# SyncScan_Standalone_MK3_PTH.net
KiCad netlist of a schematic drawn in EAGLE
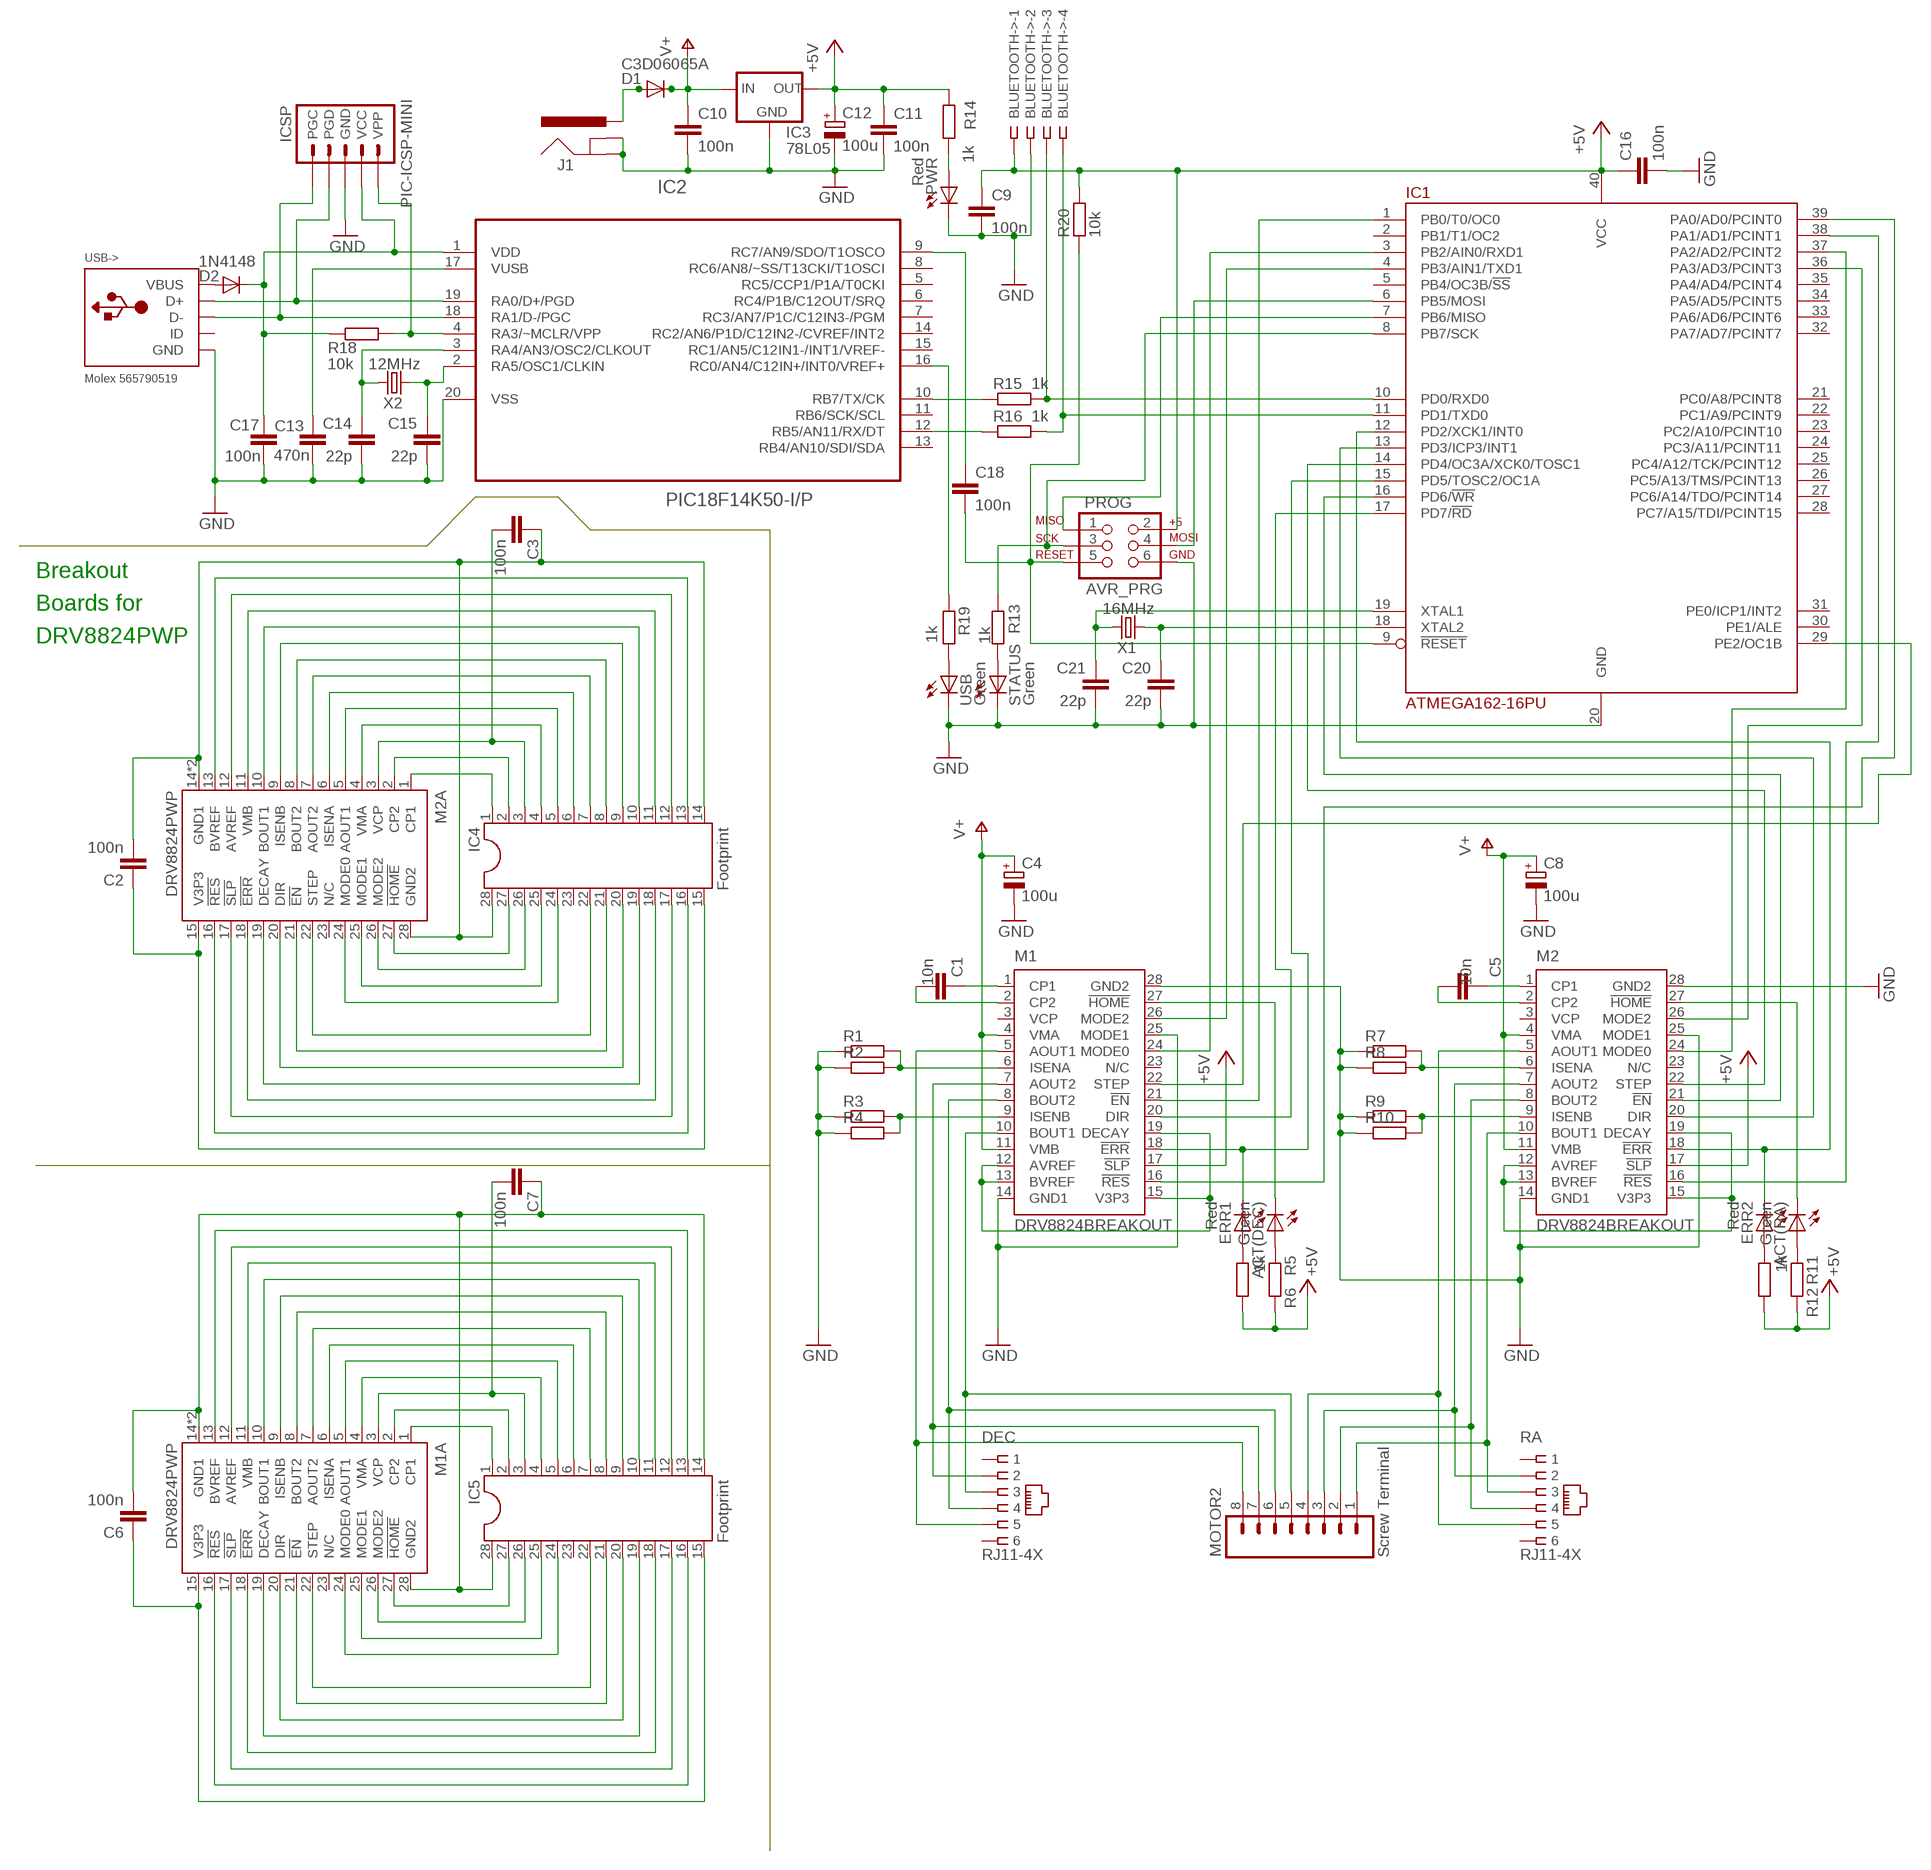
[diagram p0: schematic, sheet 1]

(export (version "E")
  (design (tool "Eeschema 10.0.6"))
  (components
    (comp (ref "ACT(DEC)")
      (value "Green")
      (footprint "eagle-import:LED3MM")
      (fields (field (name "MF") "KINGBRIGHT") (field (name "MPN") "L-424GDT"))
      (libsource (lib "eagle-import") (part "LED3MM"))
    )
    (comp (ref "ACT(RA)")
      (value "Green")
      (footprint "eagle-import:LED3MM")
      (fields (field (name "MF") "KINGBRIGHT") (field (name "MPN") "L-424GDT"))
      (libsource (lib "eagle-import") (part "LED3MM"))
    )
    (comp (ref "BLUETOOTH->")
      (value "http://www.ebay.co.uk/itm/250991624201")
      (footprint "eagle-import:SSW-104-02-S-S-RA")
      (fields (field (name "MPN") "SSW-104-02-S-S-RA") (field (name "OC_FARNELL") "unknown"))
      (libsource (lib "eagle-import") (part "SSW-104-02-S-S-RA"))
    )
    (comp (ref "C1")
      (value "10n")
      (footprint "eagle-import:C025-024X044")
      (fields (field (name "MF") "AVX") (field (name "MPN") "SR151C103KAR"))
      (libsource (lib "eagle-import") (part "resistor_C-EU025-024X044"))
    )
    (comp (ref "C2")
      (value "100n")
      (footprint "eagle-import:C0603K")
      (fields (field (name "MF") "KEMET") (field (name "MPN") "C0603C104K4RACTU"))
      (libsource (lib "eagle-import") (part "resistor_C-EUC0603K"))
    )
    (comp (ref "C3")
      (value "100n")
      (footprint "eagle-import:C0603K")
      (fields (field (name "MF") "KEMET") (field (name "MPN") "C0603C104K4RACTU"))
      (libsource (lib "eagle-import") (part "resistor_C-EUC0603K"))
    )
    (comp (ref "C4")
      (value "100u")
      (footprint "eagle-import:E2,5-6")
      (fields (field (name "MF") "MULTICOMP") (field (name "MPN") "MCGPR25V107M6.3X11"))
      (libsource (lib "eagle-import") (part "CPOL-EUE2.5-6"))
    )
    (comp (ref "C5")
      (value "10n")
      (footprint "eagle-import:C025-024X044")
      (fields (field (name "MF") "AVX") (field (name "MPN") "SR151C103KAR"))
      (libsource (lib "eagle-import") (part "resistor_C-EU025-024X044"))
    )
    (comp (ref "C6")
      (value "100n")
      (footprint "eagle-import:C0603K")
      (fields (field (name "MF") "KEMET") (field (name "MPN") "C0603C104K4RACTU"))
      (libsource (lib "eagle-import") (part "resistor_C-EUC0603K"))
    )
    (comp (ref "C7")
      (value "100n")
      (footprint "eagle-import:C0603K")
      (fields (field (name "MF") "KEMET") (field (name "MPN") "C0603C104K4RACTU"))
      (libsource (lib "eagle-import") (part "resistor_C-EUC0603K"))
    )
    (comp (ref "C8")
      (value "100u")
      (footprint "eagle-import:E2,5-6")
      (fields (field (name "MF") "MULTICOMP") (field (name "MPN") "MCGPR25V107M6.3X11"))
      (libsource (lib "eagle-import") (part "CPOL-EUE2.5-6"))
    )
    (comp (ref "C9")
      (value "100n")
      (footprint "eagle-import:C025-024X044")
      (fields (field (name "MF") "AVX") (field (name "MPN") "SR205C104KAR"))
      (libsource (lib "eagle-import") (part "resistor_C-EU025-024X044"))
    )
    (comp (ref "C10")
      (value "100n")
      (footprint "eagle-import:C025-024X044")
      (fields (field (name "MF") "AVX") (field (name "MPN") "SR205C104KAR"))
      (libsource (lib "eagle-import") (part "resistor_C-EU025-024X044"))
    )
    (comp (ref "C11")
      (value "100n")
      (footprint "eagle-import:C025-024X044")
      (fields (field (name "MF") "AVX") (field (name "MPN") "SR205C104KAR"))
      (libsource (lib "eagle-import") (part "resistor_C-EU025-024X044"))
    )
    (comp (ref "C12")
      (value "100u")
      (footprint "eagle-import:E2,5-6")
      (fields (field (name "MF") "MULTICOMP") (field (name "MPN") "MCGPR25V107M6.3X11"))
      (libsource (lib "eagle-import") (part "CPOL-EUE2.5-6"))
    )
    (comp (ref "C13")
      (value "470n")
      (footprint "eagle-import:C025-024X044")
      (fields (field (name "MF") "KEMET") (field (name "MPN") "C320C474M5U5TA"))
      (libsource (lib "eagle-import") (part "C-EU025-024X044"))
    )
    (comp (ref "C14")
      (value "22p")
      (footprint "eagle-import:C025-024X044")
      (fields (field (name "MF") "AVX") (field (name "MPN") "SR151A220JAR"))
      (libsource (lib "eagle-import") (part "C-EU025-024X044"))
    )
    (comp (ref "C15")
      (value "22p")
      (footprint "eagle-import:C025-024X044")
      (fields (field (name "MF") "AVX") (field (name "MPN") "SR151A220JAR"))
      (libsource (lib "eagle-import") (part "C-EU025-024X044"))
    )
    (comp (ref "C16")
      (value "100n")
      (footprint "eagle-import:C025-024X044")
      (fields (field (name "MF") "AVX") (field (name "MPN") "SR205C104KAR"))
      (libsource (lib "eagle-import") (part "resistor_C-EU025-024X044"))
    )
    (comp (ref "C17")
      (value "100n")
      (footprint "eagle-import:C025-024X044")
      (fields (field (name "MF") "AVX") (field (name "MPN") "SR205C104KAR"))
      (libsource (lib "eagle-import") (part "resistor_C-EU025-024X044"))
    )
    (comp (ref "C18")
      (value "100n")
      (footprint "eagle-import:C025-024X044")
      (fields (field (name "MF") "AVX") (field (name "MPN") "SR205C104KAR"))
      (libsource (lib "eagle-import") (part "resistor_C-EU025-024X044"))
    )
    (comp (ref "C20")
      (value "22p")
      (footprint "eagle-import:C025-024X044")
      (fields (field (name "MF") "AVX") (field (name "MPN") "SR151A220JAR"))
      (libsource (lib "eagle-import") (part "C-EU025-024X044"))
    )
    (comp (ref "C21")
      (value "22p")
      (footprint "eagle-import:C025-024X044")
      (fields (field (name "MF") "AVX") (field (name "MPN") "SR151A220JAR"))
      (libsource (lib "eagle-import") (part "C-EU025-024X044"))
    )
    (comp (ref "D1")
      (value "C3D06065A")
      (footprint "eagle-import:TO220ACS")
      (fields (field (name "MF") "CREE"))
      (libsource (lib "eagle-import") (part "BYW80"))
    )
    (comp (ref "D2")
      (value "1N4148")
      (footprint "eagle-import:DIODE-1N4148")
      (fields (field (name "MF") "MULTICOMP") (field (name "MPN") "1N4148."))
      (libsource (lib "eagle-import") (part "DIODE1N4148"))
    )
    (comp (ref "DEC")
      (value "RJ11-4X")
      (footprint "eagle-import:RJ11-NO_SHIELD")
      (fields
        (field (name "MPN") "6609214-3")
        (field (name "MF") "MH CONNECTORS")
        (field (name "MPN_1") "MHRJJ64NFRA")
        (field (name "OC_FARNELL") "3938347")
      )
      (libsource (lib "eagle-import") (part "RJ11-4X"))
    )
    (comp (ref "ERR1")
      (value "Red")
      (footprint "eagle-import:LED3MM")
      (fields (field (name "MF") "KINGBRIGHT") (field (name "MPN") "L-424HDT"))
      (libsource (lib "eagle-import") (part "LED3MM"))
    )
    (comp (ref "ERR2")
      (value "Red")
      (footprint "eagle-import:LED3MM")
      (fields (field (name "MF") "KINGBRIGHT") (field (name "MPN") "L-424HDT"))
      (libsource (lib "eagle-import") (part "LED3MM"))
    )
    (comp (ref "IC1")
      (value "ATMEGA162-16PU")
      (footprint "eagle-import:DIL40")
      (fields (field (name "MF") "ATMEL"))
      (libsource (lib "eagle-import") (part "ATMEGA162-16PU"))
    )
    (comp (ref "IC2")
      (value "PIC18F14K50-I/P")
      (footprint "eagle-import:DIL20")
      (fields
        (field (name "MF") "MICROCHIP")
        (field (name "MPN") "PIC18F14K50-I/P")
        (field (name "OC_FARNELL") "1648501")
      )
      (libsource (lib "eagle-import") (part "PIC18F14K50-I/P"))
    )
    (comp (ref "IC3")
      (value "78L05")
      (footprint "eagle-import:TO-92")
      (fields (field (name "MF") "FAIRCHILD SEMICONDUCTOR") (field (name "MPN") "LM78L05ACZX"))
      (libsource (lib "eagle-import") (part "V_REG_78XXTO-92"))
    )
    (comp (ref "IC4")
      (value "Footprint")
      (footprint "eagle-import:DIL28-6")
      (fields (field (name "MF") "MULTICOMP") (field (name "MPN") "MC34735"))
      (libsource (lib "eagle-import") (part "DIL28"))
    )
    (comp (ref "IC5")
      (value "Footprint")
      (footprint "eagle-import:DIL28-6")
      (fields (field (name "MF") "MULTICOMP") (field (name "MPN") "MC34735"))
      (libsource (lib "eagle-import") (part "DIL28"))
    )
    (comp (ref "ICSP")
      (value "PIC-ICSP-MINI")
      (footprint "eagle-import:PIC-ICSP-MINI")
      (libsource (lib "eagle-import") (part "PIC-ICSP-MINI"))
    )
    (comp (ref "J1")
      (value "POWER_JACKPTH")
      (footprint "eagle-import:POWER_JACK_PTH")
      (fields (field (name "MF") "MULTICOMP") (field (name "MPN") "MJ-179PH"))
      (libsource (lib "eagle-import") (part "POWER_JACKPTH"))
    )
    (comp (ref "M1")
      (value "DRV8824BREAKOUT")
      (footprint "eagle-import:DIL28-6")
      (fields (field (name "MF") "MULTICOMP") (field (name "MPN") "MC-2227-28-06-F1"))
      (libsource (lib "eagle-import") (part "DRV8824BREAKOUT"))
    )
    (comp (ref "M1A")
      (value "DRV8824PWP")
      (footprint "eagle-import:HTSSOP28PWP")
      (fields (field (name "MF") "TEXAS INSTRUMENTS"))
      (libsource (lib "eagle-import") (part "DRV8824PWP"))
    )
    (comp (ref "M2")
      (value "DRV8824BREAKOUT")
      (footprint "eagle-import:DIL28-6")
      (fields (field (name "MF") "MULTICOMP") (field (name "MPN") "MC-2227-28-06-F1"))
      (libsource (lib "eagle-import") (part "DRV8824BREAKOUT"))
    )
    (comp (ref "M2A")
      (value "DRV8824PWP")
      (footprint "eagle-import:HTSSOP28PWP")
      (fields (field (name "MF") "TEXAS INSTRUMENTS"))
      (libsource (lib "eagle-import") (part "DRV8824PWP"))
    )
    (comp (ref "MOTOR2")
      (value "Screw Terminal")
      (footprint "eagle-import:SCREWTERMINAL-3.5MM-8")
      (fields (field (name "MF") "LUMBERG") (field (name "MPN") "KRMC 08"))
      (libsource (lib "eagle-import") (part "M083.5MM-8"))
    )
    (comp (ref "PROG")
      (value "AVR_PRG")
      (footprint "eagle-import:2X3")
      (fields (field (name "MF") "TE CONNECTIVITY / AMP") (field (name "MPN") "826632-3"))
      (libsource (lib "eagle-import") (part "AVR_SPI_PRG_6PTH"))
    )
    (comp (ref "PWR")
      (value "Red")
      (footprint "eagle-import:LED3MM")
      (fields (field (name "MF") "KINGBRIGHT") (field (name "MPN") "L-424HDT"))
      (libsource (lib "eagle-import") (part "LED3MM"))
    )
    (comp (ref "R1")
      (value "1.5R")
      (footprint "eagle-import:0309_12")
      (fields (field (name "MF") "WELWYN") (field (name "MPN") "MFP1-1R5 JI"))
      (libsource (lib "eagle-import") (part "resistor_R-EU_0309/12"))
    )
    (comp (ref "R2")
      (value "1.5R")
      (footprint "eagle-import:0309_12")
      (fields (field (name "MF") "WELWYN") (field (name "MPN") "MFP1-1R5 JI"))
      (libsource (lib "eagle-import") (part "resistor_R-EU_0309/12"))
    )
    (comp (ref "R3")
      (value "1.5R")
      (footprint "eagle-import:0309_12")
      (fields (field (name "MF") "WELWYN") (field (name "MPN") "MFP1-1R5 JI"))
      (libsource (lib "eagle-import") (part "resistor_R-EU_0309/12"))
    )
    (comp (ref "R4")
      (value "1.5R")
      (footprint "eagle-import:0309_12")
      (fields (field (name "MF") "WELWYN") (field (name "MPN") "MFP1-1R5 JI"))
      (libsource (lib "eagle-import") (part "resistor_R-EU_0309/12"))
    )
    (comp (ref "R5")
      (value "1k")
      (footprint "eagle-import:0204_7")
      (fields (field (name "MF") "MULTICOMP") (field (name "MPN") "MF12 1K"))
      (libsource (lib "eagle-import") (part "resistor_R-EU_0204/7"))
    )
    (comp (ref "R6")
      (value "1k")
      (footprint "eagle-import:0204_7")
      (fields (field (name "MF") "MULTICOMP") (field (name "MPN") "MF12 1K"))
      (libsource (lib "eagle-import") (part "resistor_R-EU_0204/7"))
    )
    (comp (ref "R7")
      (value "1.5R")
      (footprint "eagle-import:0309_12")
      (fields (field (name "MF") "WELWYN") (field (name "MPN") "MFP1-1R5 JI"))
      (libsource (lib "eagle-import") (part "resistor_R-EU_0309/12"))
    )
    (comp (ref "R8")
      (value "1.5R")
      (footprint "eagle-import:0309_12")
      (fields (field (name "MF") "WELWYN") (field (name "MPN") "MFP1-1R5 JI"))
      (libsource (lib "eagle-import") (part "resistor_R-EU_0309/12"))
    )
    (comp (ref "R9")
      (value "1.5R")
      (footprint "eagle-import:0309_12")
      (fields (field (name "MF") "WELWYN") (field (name "MPN") "MFP1-1R5 JI"))
      (libsource (lib "eagle-import") (part "resistor_R-EU_0309/12"))
    )
    (comp (ref "R10")
      (value "1.5R")
      (footprint "eagle-import:0309_12")
      (fields (field (name "MF") "WELWYN") (field (name "MPN") "MFP1-1R5 JI"))
      (libsource (lib "eagle-import") (part "resistor_R-EU_0309/12"))
    )
    (comp (ref "R11")
      (value "1k")
      (footprint "eagle-import:0204_7")
      (fields (field (name "MF") "MULTICOMP") (field (name "MPN") "MF12 1K"))
      (libsource (lib "eagle-import") (part "resistor_R-EU_0204/7"))
    )
    (comp (ref "R12")
      (value "1k")
      (footprint "eagle-import:0204_7")
      (fields (field (name "MF") "MULTICOMP") (field (name "MPN") "MF12 1K"))
      (libsource (lib "eagle-import") (part "resistor_R-EU_0204/7"))
    )
    (comp (ref "R13")
      (value "1k")
      (footprint "eagle-import:0204_7")
      (fields (field (name "MF") "MULTICOMP") (field (name "MPN") "MF12 1K"))
      (libsource (lib "eagle-import") (part "rcl_R-EU_0204/7"))
    )
    (comp (ref "R14")
      (value "1k")
      (footprint "eagle-import:0204_7")
      (fields (field (name "MF") "MULTICOMP") (field (name "MPN") "MF12 1K"))
      (libsource (lib "eagle-import") (part "rcl_R-EU_0204/7"))
    )
    (comp (ref "R15")
      (value "1k")
      (footprint "eagle-import:0204_7")
      (fields (field (name "MF") "MULTICOMP") (field (name "MPN") "MF12 1K"))
      (libsource (lib "eagle-import") (part "R-EU_0204/7"))
    )
    (comp (ref "R16")
      (value "1k")
      (footprint "eagle-import:0204_7")
      (fields (field (name "MF") "MULTICOMP") (field (name "MPN") "MF12 1K"))
      (libsource (lib "eagle-import") (part "R-EU_0204/7"))
    )
    (comp (ref "R18")
      (value "10k")
      (footprint "eagle-import:0204_7")
      (fields (field (name "MF") "MULTICOMP") (field (name "MPN") "MF12 10K"))
      (libsource (lib "eagle-import") (part "rcl_R-EU_0204/7"))
    )
    (comp (ref "R19")
      (value "1k")
      (footprint "eagle-import:0204_7")
      (fields (field (name "MF") "MULTICOMP") (field (name "MPN") "MF12 1K"))
      (libsource (lib "eagle-import") (part "rcl_R-EU_0204/7"))
    )
    (comp (ref "R20")
      (value "10k")
      (footprint "eagle-import:0204_7")
      (fields (field (name "MF") "MULTICOMP") (field (name "MPN") "MF12 10K"))
      (libsource (lib "eagle-import") (part "rcl_R-EU_0204/7"))
    )
    (comp (ref "RA")
      (value "RJ11-4X")
      (footprint "eagle-import:RJ11-NO_SHIELD")
      (fields
        (field (name "MPN") "6609214-3")
        (field (name "MF") "MH CONNECTORS")
        (field (name "MPN_1") "MHRJJ64NFRA")
        (field (name "OC_FARNELL") "3938347")
      )
      (libsource (lib "eagle-import") (part "RJ11-4X"))
    )
    (comp (ref "STATUS")
      (value "Green")
      (footprint "eagle-import:LED3MM")
      (fields (field (name "MF") "KINGBRIGHT") (field (name "MPN") "L-424GDT"))
      (libsource (lib "eagle-import") (part "LED3MM"))
    )
    (comp (ref "USB")
      (value "Green")
      (footprint "eagle-import:LED3MM")
      (fields (field (name "MF") "KINGBRIGHT") (field (name "MPN") "L-424GDT"))
      (libsource (lib "eagle-import") (part "LED3MM"))
    )
    (comp (ref "USB->")
      (value "Molex 565790519")
      (footprint "eagle-import:USB-MINIB-THM-MOLEX")
      (fields (field (name "MF") "MOLEX") (field (name "MPN") "565790519"))
      (libsource (lib "eagle-import") (part "USBMOLEX"))
    )
    (comp (ref "X1")
      (value "16MHz")
      (footprint "eagle-import:HC49US")
      (fields (field (name "MF") "TXC") (field (name "MPN") "9B-16.000MEEJ-B"))
      (libsource (lib "eagle-import") (part "CRYSTALHC49US"))
    )
    (comp (ref "X2")
      (value "12MHz")
      (footprint "eagle-import:HC49US")
      (fields (field (name "MF") "TXC") (field (name "MPN") "9B-12.000MAAJ-B"))
      (libsource (lib "eagle-import") (part "CRYSTALHC49US"))
    )
  )
  (nets
    (net (code "1") (name "+5V") (class "Default")
      (node (ref "BLUETOOTH->") (pin "1") (pinfunction "1_1") (pintype "passive"))
      (node (ref "C11") (pin "1") (pinfunction "1_1") (pintype "passive"))
      (node (ref "C12") (pin "+") (pinfunction "+_+") (pintype "passive"))
      (node (ref "C16") (pin "1") (pinfunction "1_1") (pintype "passive"))
      (node (ref "C9") (pin "1") (pinfunction "1_1") (pintype "passive"))
      (node (ref "IC1") (pin "40") (pinfunction "VCC_40") (pintype "power_in"))
      (node (ref "IC3") (pin "1") (pinfunction "OUT_1") (pintype "power_in"))
      (node (ref "M1") (pin "17") (pinfunction "~{SLP}_17") (pintype "input"))
      (node (ref "M2") (pin "17") (pinfunction "~{SLP}_17") (pintype "input"))
      (node (ref "PROG") (pin "2") (pinfunction "2_2") (pintype "passive"))
      (node (ref "R11") (pin "2") (pinfunction "2_2") (pintype "passive"))
      (node (ref "R12") (pin "2") (pinfunction "2_2") (pintype "passive"))
      (node (ref "R14") (pin "1") (pinfunction "1_1") (pintype "passive"))
      (node (ref "R20") (pin "2") (pinfunction "2_2") (pintype "passive"))
      (node (ref "R5") (pin "2") (pinfunction "2_2") (pintype "passive"))
      (node (ref "R6") (pin "2") (pinfunction "2_2") (pintype "passive"))
    )
    (net (code "2") (name "GND") (class "Default")
      (node (ref "BLUETOOTH->") (pin "2") (pinfunction "1_2") (pintype "passive"))
      (node (ref "C10") (pin "2") (pinfunction "2_2") (pintype "passive"))
      (node (ref "C11") (pin "2") (pinfunction "2_2") (pintype "passive"))
      (node (ref "C12") (pin "-") (pinfunction "-_-") (pintype "passive"))
      (node (ref "C13") (pin "1") (pinfunction "1_1") (pintype "passive"))
      (node (ref "C14") (pin "2") (pinfunction "2_2") (pintype "passive"))
      (node (ref "C15") (pin "2") (pinfunction "2_2") (pintype "passive"))
      (node (ref "C16") (pin "2") (pinfunction "2_2") (pintype "passive"))
      (node (ref "C17") (pin "2") (pinfunction "2_2") (pintype "passive"))
      (node (ref "C20") (pin "2") (pinfunction "2_2") (pintype "passive"))
      (node (ref "C21") (pin "2") (pinfunction "2_2") (pintype "passive"))
      (node (ref "C4") (pin "-") (pinfunction "-_-") (pintype "passive"))
      (node (ref "C8") (pin "-") (pinfunction "-_-") (pintype "passive"))
      (node (ref "C9") (pin "2") (pinfunction "2_2") (pintype "passive"))
      (node (ref "IC1") (pin "20") (pinfunction "GND_20") (pintype "power_in"))
      (node (ref "IC2") (pin "20") (pinfunction "VSS_20") (pintype "power_in"))
      (node (ref "IC3") (pin "2") (pinfunction "GND_2") (pintype "input"))
      (node (ref "ICSP") (pin "3") (pinfunction "GND_3") (pintype "passive"))
      (node (ref "J1") (pin "GND") (pinfunction "GND_GND") (pintype "bidirectional"))
      (node (ref "J1") (pin "GNDBREAK") (pinfunction "GNDBREAK_GNDBREAK") (pintype "bidirectional"))
      (node (ref "M1") (pin "14") (pinfunction "GND1_14") (pintype "power_in"))
      (node (ref "M1") (pin "25") (pinfunction "MODE1_25") (pintype "input"))
      (node (ref "M1") (pin "28") (pinfunction "GND2_28") (pintype "power_in"))
      (node (ref "M2") (pin "14") (pinfunction "GND1_14") (pintype "power_in"))
      (node (ref "M2") (pin "25") (pinfunction "MODE1_25") (pintype "input"))
      (node (ref "M2") (pin "28") (pinfunction "GND2_28") (pintype "power_in"))
      (node (ref "PROG") (pin "6") (pinfunction "6_6") (pintype "passive"))
      (node (ref "PWR") (pin "K") (pinfunction "C_K") (pintype "passive"))
      (node (ref "R1") (pin "1") (pinfunction "1_1") (pintype "passive"))
      (node (ref "R10") (pin "1") (pinfunction "1_1") (pintype "passive"))
      (node (ref "R2") (pin "1") (pinfunction "1_1") (pintype "passive"))
      (node (ref "R3") (pin "1") (pinfunction "1_1") (pintype "passive"))
      (node (ref "R4") (pin "1") (pinfunction "1_1") (pintype "passive"))
      (node (ref "R7") (pin "1") (pinfunction "1_1") (pintype "passive"))
      (node (ref "R8") (pin "1") (pinfunction "1_1") (pintype "passive"))
      (node (ref "R9") (pin "1") (pinfunction "1_1") (pintype "passive"))
      (node (ref "STATUS") (pin "K") (pinfunction "C_K") (pintype "passive"))
      (node (ref "USB") (pin "K") (pinfunction "C_K") (pintype "passive"))
      (node (ref "USB->") (pin "GND") (pinfunction "GND_GND") (pintype "power_in"))
    )
    (net (code "3") (name "Net-(ACT(DEC)-C)") (class "Default")
      (node (ref "ACT(DEC)") (pin "K") (pinfunction "C_K") (pintype "passive"))
      (node (ref "M1") (pin "27") (pinfunction "~{HOME}_27") (pintype "output"))
    )
    (net (code "4") (name "Net-(ACT(DEC)-PadA)") (class "Default")
      (node (ref "ACT(DEC)") (pin "A") (pinfunction "A_A") (pintype "passive"))
      (node (ref "R5") (pin "1") (pinfunction "1_1") (pintype "passive"))
    )
    (net (code "5") (name "Net-(ACT(RA)-C)") (class "Default")
      (node (ref "ACT(RA)") (pin "K") (pinfunction "C_K") (pintype "passive"))
      (node (ref "M2") (pin "27") (pinfunction "~{HOME}_27") (pintype "output"))
    )
    (net (code "6") (name "Net-(ACT(RA)-PadA)") (class "Default")
      (node (ref "ACT(RA)") (pin "A") (pinfunction "A_A") (pintype "passive"))
      (node (ref "R11") (pin "1") (pinfunction "1_1") (pintype "passive"))
    )
    (net (code "7") (name "Net-(BLUETOOTH->C-1)") (class "Default")
      (node (ref "BLUETOOTH->") (pin "3") (pinfunction "1_3") (pintype "passive"))
      (node (ref "IC1") (pin "10") (pinfunction "PD0/RXD0_10") (pintype "bidirectional"))
      (node (ref "R15") (pin "1") (pinfunction "1_1") (pintype "passive"))
    )
    (net (code "8") (name "Net-(BLUETOOTH->D-1)") (class "Default")
      (node (ref "BLUETOOTH->") (pin "4") (pinfunction "1_4") (pintype "passive"))
      (node (ref "IC1") (pin "11") (pinfunction "PD1/TXD0_11") (pintype "bidirectional"))
      (node (ref "R16") (pin "1") (pinfunction "1_1") (pintype "passive"))
    )
    (net (code "9") (name "Net-(D1-PadA)") (class "Default")
      (node (ref "D1") (pin "A") (pinfunction "A_A") (pintype "passive"))
      (node (ref "J1") (pin "PWR") (pinfunction "PWR_PWR") (pintype "bidirectional"))
    )
    (net (code "10") (name "Net-(D2-PadA)") (class "Default")
      (node (ref "D2") (pin "A") (pinfunction "A_A") (pintype "passive"))
      (node (ref "USB->") (pin "VBUS") (pinfunction "VBUS_VBUS") (pintype "power_in"))
    )
    (net (code "11") (name "Net-(ERR1-C)") (class "Default")
      (node (ref "ERR1") (pin "K") (pinfunction "C_K") (pintype "passive"))
      (node (ref "IC1") (pin "15") (pinfunction "PD5/TOSC2/OC1A_15") (pintype "bidirectional"))
      (node (ref "M1") (pin "18") (pinfunction "~{ERR}_18") (pintype "output"))
    )
    (net (code "12") (name "Net-(ERR1-PadA)") (class "Default")
      (node (ref "ERR1") (pin "A") (pinfunction "A_A") (pintype "passive"))
      (node (ref "R6") (pin "1") (pinfunction "1_1") (pintype "passive"))
    )
    (net (code "13") (name "Net-(ERR2-C)") (class "Default")
      (node (ref "ERR2") (pin "K") (pinfunction "C_K") (pintype "passive"))
      (node (ref "IC1") (pin "12") (pinfunction "PD2/XCK1/INT0_12") (pintype "bidirectional"))
      (node (ref "M2") (pin "18") (pinfunction "~{ERR}_18") (pintype "output"))
    )
    (net (code "14") (name "Net-(ERR2-PadA)") (class "Default")
      (node (ref "ERR2") (pin "A") (pinfunction "A_A") (pintype "passive"))
      (node (ref "R12") (pin "1") (pinfunction "1_1") (pintype "passive"))
    )
    (net (code "15") (name "Net-(IC1-PA0{slash}AD0{slash}PCINT0)") (class "Default")
      (node (ref "IC1") (pin "39") (pinfunction "PA0/AD0/PCINT0_39") (pintype "bidirectional"))
      (node (ref "M1") (pin "16") (pinfunction "~{RES}_16") (pintype "input"))
    )
    (net (code "16") (name "Net-(IC1-PA1{slash}AD1{slash}PCINT1)") (class "Default")
      (node (ref "IC1") (pin "38") (pinfunction "PA1/AD1/PCINT1_38") (pintype "bidirectional"))
      (node (ref "M2") (pin "16") (pinfunction "~{RES}_16") (pintype "input"))
    )
    (net (code "17") (name "Net-(IC1-PA2{slash}AD2{slash}PCINT2)") (class "Default")
      (node (ref "IC1") (pin "37") (pinfunction "PA2/AD2/PCINT2_37") (pintype "bidirectional"))
      (node (ref "M2") (pin "24") (pinfunction "MODE0_24") (pintype "input"))
    )
    (net (code "18") (name "Net-(IC1-PA3{slash}AD3{slash}PCINT3)") (class "Default")
      (node (ref "IC1") (pin "36") (pinfunction "PA3/AD3/PCINT3_36") (pintype "bidirectional"))
      (node (ref "M2") (pin "26") (pinfunction "MODE2_26") (pintype "input"))
    )
    (net (code "19") (name "Net-(IC1-PB0{slash}T0{slash}OC0)") (class "Default")
      (node (ref "IC1") (pin "1") (pinfunction "PB0/T0/OC0_1") (pintype "bidirectional"))
      (node (ref "M1") (pin "21") (pinfunction "~{EN}_21") (pintype "input"))
    )
    (net (code "20") (name "Net-(IC1-PB2{slash}AIN0{slash}RXD1)") (class "Default")
      (node (ref "IC1") (pin "3") (pinfunction "PB2/AIN0/RXD1_3") (pintype "bidirectional"))
      (node (ref "M1") (pin "24") (pinfunction "MODE0_24") (pintype "input"))
    )
    (net (code "21") (name "Net-(IC1-PB3{slash}AIN1{slash}TXD1)") (class "Default")
      (node (ref "IC1") (pin "4") (pinfunction "PB3/AIN1/TXD1_4") (pintype "bidirectional"))
      (node (ref "M1") (pin "26") (pinfunction "MODE2_26") (pintype "input"))
    )
    (net (code "22") (name "Net-(IC1-PB5{slash}MOSI)") (class "Default")
      (node (ref "IC1") (pin "6") (pinfunction "PB5/MOSI_6") (pintype "bidirectional"))
      (node (ref "PROG") (pin "4") (pinfunction "4_4") (pintype "passive"))
    )
    (net (code "23") (name "Net-(IC1-PB6{slash}MISO)") (class "Default")
      (node (ref "IC1") (pin "7") (pinfunction "PB6/MISO_7") (pintype "bidirectional"))
      (node (ref "PROG") (pin "1") (pinfunction "1_1") (pintype "passive"))
    )
    (net (code "24") (name "Net-(IC1-PB7{slash}SCK)") (class "Default")
      (node (ref "IC1") (pin "8") (pinfunction "PB7/SCK_8") (pintype "bidirectional"))
      (node (ref "PROG") (pin "3") (pinfunction "3_3") (pintype "passive"))
      (node (ref "R13") (pin "1") (pinfunction "1_1") (pintype "passive"))
    )
    (net (code "25") (name "Net-(IC1-PD3{slash}ICP3{slash}INT1)") (class "Default")
      (node (ref "IC1") (pin "13") (pinfunction "PD3/ICP3/INT1_13") (pintype "bidirectional"))
      (node (ref "M2") (pin "20") (pinfunction "DIR_20") (pintype "input"))
    )
    (net (code "26") (name "Net-(IC1-PD4{slash}OC3A{slash}XCK0{slash}TOSC1)") (class "Default")
      (node (ref "IC1") (pin "14") (pinfunction "PD4/OC3A/XCK0/TOSC1_14") (pintype "bidirectional"))
      (node (ref "M2") (pin "22") (pinfunction "STEP_22") (pintype "input"))
    )
    (net (code "27") (name "Net-(IC1-PD6{slash}~{WR})") (class "Default")
      (node (ref "IC1") (pin "16") (pinfunction "PD6/~{WR}_16") (pintype "bidirectional"))
      (node (ref "M2") (pin "21") (pinfunction "~{EN}_21") (pintype "input"))
    )
    (net (code "28") (name "Net-(IC1-PD7{slash}~{RD})") (class "Default")
      (node (ref "IC1") (pin "17") (pinfunction "PD7/~{RD}_17") (pintype "bidirectional"))
      (node (ref "M1") (pin "20") (pinfunction "DIR_20") (pintype "input"))
    )
    (net (code "29") (name "Net-(IC1-PE2{slash}OC1B)") (class "Default")
      (node (ref "IC1") (pin "29") (pinfunction "PE2/OC1B_29") (pintype "bidirectional"))
      (node (ref "M1") (pin "22") (pinfunction "STEP_22") (pintype "input"))
    )
    (net (code "30") (name "Net-(IC1-XTAL1)") (class "Default")
      (node (ref "C21") (pin "1") (pinfunction "1_1") (pintype "passive"))
      (node (ref "IC1") (pin "19") (pinfunction "XTAL1_19") (pintype "input"))
      (node (ref "X1") (pin "2") (pinfunction "2_2") (pintype "passive"))
    )
    (net (code "31") (name "Net-(IC1-XTAL2)") (class "Default")
      (node (ref "C20") (pin "1") (pinfunction "1_1") (pintype "passive"))
      (node (ref "IC1") (pin "18") (pinfunction "XTAL2_18") (pintype "input"))
      (node (ref "X1") (pin "1") (pinfunction "1_1") (pintype "passive"))
    )
    (net (code "32") (name "Net-(IC1-~{RESET})") (class "Default")
      (node (ref "C18") (pin "2") (pinfunction "2_2") (pintype "passive"))
      (node (ref "IC1") (pin "9") (pinfunction "~{RESET}_9") (pintype "input"))
      (node (ref "PROG") (pin "5") (pinfunction "5_5") (pintype "passive"))
      (node (ref "R20") (pin "1") (pinfunction "1_1") (pintype "passive"))
    )
    (net (code "33") (name "Net-(IC2-RA0{slash}D+{slash}PGD)") (class "Default")
      (node (ref "IC2") (pin "19") (pinfunction "RA0/D+/PGD_19") (pintype "bidirectional"))
      (node (ref "ICSP") (pin "4") (pinfunction "PGD_4") (pintype "passive"))
      (node (ref "USB->") (pin "D+") (pinfunction "D+_D+") (pintype "bidirectional"))
    )
    (net (code "34") (name "Net-(IC2-RA1{slash}D-{slash}PGC)") (class "Default")
      (node (ref "IC2") (pin "18") (pinfunction "RA1/D-/PGC_18") (pintype "bidirectional"))
      (node (ref "ICSP") (pin "5") (pinfunction "PGC_5") (pintype "passive"))
      (node (ref "USB->") (pin "D-") (pinfunction "D-_D-") (pintype "bidirectional"))
    )
    (net (code "35") (name "Net-(IC2-RA3{slash}~{MCLR{slash}VPP})") (class "Default")
      (node (ref "IC2") (pin "4") (pinfunction "RA3/~{MCLR/VPP}_4") (pintype "input"))
      (node (ref "ICSP") (pin "1") (pinfunction "VPP_1") (pintype "passive"))
      (node (ref "R18") (pin "1") (pinfunction "1_1") (pintype "passive"))
    )
    (net (code "36") (name "Net-(IC2-RA4{slash}AN3{slash}OSC2{slash}CLKOUT)") (class "Default")
      (node (ref "C14") (pin "1") (pinfunction "1_1") (pintype "passive"))
      (node (ref "IC2") (pin "3") (pinfunction "RA4/AN3/OSC2/CLKOUT_3") (pintype "bidirectional"))
      (node (ref "X2") (pin "2") (pinfunction "2_2") (pintype "passive"))
    )
    (net (code "37") (name "Net-(IC2-RA5{slash}OSC1{slash}CLKIN)") (class "Default")
      (node (ref "C15") (pin "1") (pinfunction "1_1") (pintype "passive"))
      (node (ref "IC2") (pin "2") (pinfunction "RA5/OSC1/CLKIN_2") (pintype "bidirectional"))
      (node (ref "X2") (pin "1") (pinfunction "1_1") (pintype "passive"))
    )
    (net (code "38") (name "Net-(IC2-RB5{slash}AN11{slash}RX{slash}DT)") (class "Default")
      (node (ref "IC2") (pin "12") (pinfunction "RB5/AN11/RX/DT_12") (pintype "bidirectional"))
      (node (ref "R16") (pin "2") (pinfunction "2_2") (pintype "passive"))
    )
    (net (code "39") (name "Net-(IC2-RB7{slash}TX{slash}CK)") (class "Default")
      (node (ref "IC2") (pin "10") (pinfunction "RB7/TX/CK_10") (pintype "bidirectional"))
      (node (ref "R15") (pin "2") (pinfunction "2_2") (pintype "passive"))
    )
    (net (code "40") (name "Net-(IC2-RC0{slash}AN4{slash}C12IN+{slash}INT0{slash}VREF+)") (class "Default")
      (node (ref "IC2") (pin "16") (pinfunction "RC0/AN4/C12IN+/INT0/VREF+_16") (pintype "bidirectional"))
      (node (ref "R19") (pin "2") (pinfunction "2_2") (pintype "passive"))
    )
    (net (code "41") (name "Net-(IC2-RC7{slash}AN9{slash}SDO{slash}T1OSCO)") (class "Default")
      (node (ref "C18") (pin "1") (pinfunction "1_1") (pintype "passive"))
      (node (ref "IC2") (pin "9") (pinfunction "RC7/AN9/SDO/T1OSCO_9") (pintype "bidirectional"))
    )
    (net (code "42") (name "Net-(IC2-VDD)") (class "Default")
      (node (ref "C17") (pin "1") (pinfunction "1_1") (pintype "passive"))
      (node (ref "D2") (pin "C") (pinfunction "C_C") (pintype "passive"))
      (node (ref "IC2") (pin "1") (pinfunction "VDD_1") (pintype "power_in"))
      (node (ref "ICSP") (pin "2") (pinfunction "VCC_2") (pintype "passive"))
      (node (ref "R18") (pin "2") (pinfunction "2_2") (pintype "passive"))
    )
    (net (code "43") (name "Net-(IC2-VUSB)") (class "Default")
      (node (ref "C13") (pin "2") (pinfunction "2_2") (pintype "passive"))
      (node (ref "IC2") (pin "17") (pinfunction "VUSB_17") (pintype "power_in"))
    )
    (net (code "44") (name "Net-(M1-AOUT1)") (class "Default")
      (node (ref "DEC") (pin "5") (pinfunction "5_5") (pintype "passive"))
      (node (ref "M1") (pin "5") (pinfunction "AOUT1_5") (pintype "output"))
      (node (ref "MOTOR2") (pin "8") (pinfunction "8_8") (pintype "passive"))
    )
    (net (code "45") (name "Net-(M1-AOUT2)") (class "Default")
      (node (ref "DEC") (pin "2") (pinfunction "2_2") (pintype "passive"))
      (node (ref "M1") (pin "7") (pinfunction "AOUT2_7") (pintype "output"))
      (node (ref "MOTOR2") (pin "7") (pinfunction "7_7") (pintype "passive"))
    )
    (net (code "46") (name "Net-(M1-AVREF)") (class "Default")
      (node (ref "M1") (pin "12") (pinfunction "AVREF_12") (pintype "input"))
      (node (ref "M1") (pin "13") (pinfunction "BVREF_13") (pintype "input"))
      (node (ref "M1") (pin "15") (pinfunction "V3P3_15") (pintype "output"))
      (node (ref "M1") (pin "19") (pinfunction "DECAY_19") (pintype "input"))
    )
    (net (code "47") (name "Net-(M1-BOUT1)") (class "Default")
      (node (ref "DEC") (pin "3") (pinfunction "3_3") (pintype "passive"))
      (node (ref "M1") (pin "10") (pinfunction "BOUT1_10") (pintype "output"))
      (node (ref "MOTOR2") (pin "5") (pinfunction "5_5") (pintype "passive"))
    )
    (net (code "48") (name "Net-(M1-BOUT2)") (class "Default")
      (node (ref "DEC") (pin "4") (pinfunction "4_4") (pintype "passive"))
      (node (ref "M1") (pin "8") (pinfunction "BOUT2_8") (pintype "output"))
      (node (ref "MOTOR2") (pin "6") (pinfunction "6_6") (pintype "passive"))
    )
    (net (code "49") (name "Net-(M1-CP1)") (class "Default")
      (node (ref "C1") (pin "1") (pinfunction "1_1") (pintype "passive"))
      (node (ref "M1") (pin "1") (pinfunction "CP1_1") (pintype "passive"))
    )
    (net (code "50") (name "Net-(M1-CP2)") (class "Default")
      (node (ref "C1") (pin "2") (pinfunction "2_2") (pintype "passive"))
      (node (ref "M1") (pin "2") (pinfunction "CP2_2") (pintype "passive"))
    )
    (net (code "51") (name "Net-(M1-ISENA)") (class "Default")
      (node (ref "M1") (pin "6") (pinfunction "ISENA_6") (pintype "bidirectional"))
      (node (ref "R1") (pin "2") (pinfunction "2_2") (pintype "passive"))
      (node (ref "R2") (pin "2") (pinfunction "2_2") (pintype "passive"))
    )
    (net (code "52") (name "Net-(M1-ISENB)") (class "Default")
      (node (ref "M1") (pin "9") (pinfunction "ISENB_9") (pintype "bidirectional"))
      (node (ref "R3") (pin "2") (pinfunction "2_2") (pintype "passive"))
      (node (ref "R4") (pin "2") (pinfunction "2_2") (pintype "passive"))
    )
    (net (code "53") (name "Net-(M1A-AOUT1)") (class "Default")
      (node (ref "IC5") (pin "5") (pinfunction "5_5") (pintype "passive"))
      (node (ref "M1A") (pin "5") (pinfunction "AOUT1_5") (pintype "output"))
    )
    (net (code "54") (name "Net-(M1A-AOUT2)") (class "Default")
      (node (ref "IC5") (pin "7") (pinfunction "7_7") (pintype "passive"))
      (node (ref "M1A") (pin "7") (pinfunction "AOUT2_7") (pintype "output"))
    )
    (net (code "55") (name "Net-(M1A-AVREF)") (class "Default")
      (node (ref "IC5") (pin "12") (pinfunction "12_12") (pintype "passive"))
      (node (ref "M1A") (pin "12") (pinfunction "AVREF_12") (pintype "input"))
    )
    (net (code "56") (name "Net-(M1A-BOUT1)") (class "Default")
      (node (ref "IC5") (pin "10") (pinfunction "10_10") (pintype "passive"))
      (node (ref "M1A") (pin "10") (pinfunction "BOUT1_10") (pintype "output"))
    )
    (net (code "57") (name "Net-(M1A-BOUT2)") (class "Default")
      (node (ref "IC5") (pin "8") (pinfunction "8_8") (pintype "passive"))
      (node (ref "M1A") (pin "8") (pinfunction "BOUT2_8") (pintype "output"))
    )
    (net (code "58") (name "Net-(M1A-BVREF)") (class "Default")
      (node (ref "IC5") (pin "13") (pinfunction "13_13") (pintype "passive"))
      (node (ref "M1A") (pin "13") (pinfunction "BVREF_13") (pintype "input"))
    )
    (net (code "59") (name "Net-(M1A-CP1)") (class "Default")
      (node (ref "IC5") (pin "1") (pinfunction "1_1") (pintype "passive"))
      (node (ref "M1A") (pin "1") (pinfunction "CP1_1") (pintype "passive"))
    )
    (net (code "60") (name "Net-(M1A-CP2)") (class "Default")
      (node (ref "IC5") (pin "2") (pinfunction "2_2") (pintype "passive"))
      (node (ref "M1A") (pin "2") (pinfunction "CP2_2") (pintype "passive"))
    )
    (net (code "61") (name "Net-(M1A-DECAY)") (class "Default")
      (node (ref "IC5") (pin "19") (pinfunction "19_19") (pintype "passive"))
      (node (ref "M1A") (pin "19") (pinfunction "DECAY_19") (pintype "input"))
    )
    (net (code "62") (name "Net-(M1A-DIR)") (class "Default")
      (node (ref "IC5") (pin "20") (pinfunction "20_20") (pintype "passive"))
      (node (ref "M1A") (pin "20") (pinfunction "DIR_20") (pintype "input"))
    )
    (net (code "63") (name "Net-(M1A-GND2)") (class "Default")
      (node (ref "C6") (pin "2") (pinfunction "2_2") (pintype "passive"))
      (node (ref "C7") (pin "1") (pinfunction "1_1") (pintype "passive"))
      (node (ref "IC5") (pin "14") (pinfunction "14_14") (pintype "passive"))
      (node (ref "IC5") (pin "28") (pinfunction "28_28") (pintype "passive"))
      (node (ref "M1A") (pin "14") (pinfunction "GND1_14") (pintype "power_in"))
      (node (ref "M1A") (pin "28") (pinfunction "GND2_28") (pintype "power_in"))
      (node (ref "M1A") (pin "EXP") (pinfunction "GND1_EXP") (pintype "power_in"))
    )
    (net (code "64") (name "Net-(M1A-ISENA)") (class "Default")
      (node (ref "IC5") (pin "6") (pinfunction "6_6") (pintype "passive"))
      (node (ref "M1A") (pin "6") (pinfunction "ISENA_6") (pintype "bidirectional"))
    )
    (net (code "65") (name "Net-(M1A-ISENB)") (class "Default")
      (node (ref "IC5") (pin "9") (pinfunction "9_9") (pintype "passive"))
      (node (ref "M1A") (pin "9") (pinfunction "ISENB_9") (pintype "bidirectional"))
    )
    (net (code "66") (name "Net-(M1A-MODE0)") (class "Default")
      (node (ref "IC5") (pin "24") (pinfunction "24_24") (pintype "passive"))
      (node (ref "M1A") (pin "24") (pinfunction "MODE0_24") (pintype "input"))
    )
    (net (code "67") (name "Net-(M1A-MODE1)") (class "Default")
      (node (ref "IC5") (pin "25") (pinfunction "25_25") (pintype "passive"))
      (node (ref "M1A") (pin "25") (pinfunction "MODE1_25") (pintype "input"))
    )
    (net (code "68") (name "Net-(M1A-MODE2)") (class "Default")
      (node (ref "IC5") (pin "26") (pinfunction "26_26") (pintype "passive"))
      (node (ref "M1A") (pin "26") (pinfunction "MODE2_26") (pintype "input"))
    )
    (net (code "69") (name "Net-(M1A-STEP)") (class "Default")
      (node (ref "IC5") (pin "22") (pinfunction "22_22") (pintype "passive"))
      (node (ref "M1A") (pin "22") (pinfunction "STEP_22") (pintype "input"))
    )
    (net (code "70") (name "Net-(M1A-V3P3)") (class "Default")
      (node (ref "C6") (pin "1") (pinfunction "1_1") (pintype "passive"))
      (node (ref "IC5") (pin "15") (pinfunction "15_15") (pintype "passive"))
      (node (ref "M1A") (pin "15") (pinfunction "V3P3_15") (pintype "output"))
    )
    (net (code "71") (name "Net-(M1A-VCP)") (class "Default")
      (node (ref "C7") (pin "2") (pinfunction "2_2") (pintype "passive"))
      (node (ref "IC5") (pin "3") (pinfunction "3_3") (pintype "passive"))
      (node (ref "M1A") (pin "3") (pinfunction "VCP_3") (pintype "output"))
    )
    (net (code "72") (name "Net-(M1A-VMA)") (class "Default")
      (node (ref "IC5") (pin "4") (pinfunction "4_4") (pintype "passive"))
      (node (ref "M1A") (pin "4") (pinfunction "VMA_4") (pintype "power_in"))
    )
    (net (code "73") (name "Net-(M1A-VMB)") (class "Default")
      (node (ref "IC5") (pin "11") (pinfunction "11_11") (pintype "passive"))
      (node (ref "M1A") (pin "11") (pinfunction "VMB_11") (pintype "power_in"))
    )
    (net (code "74") (name "Net-(M1A-~{EN})") (class "Default")
      (node (ref "IC5") (pin "21") (pinfunction "21_21") (pintype "passive"))
      (node (ref "M1A") (pin "21") (pinfunction "~{EN}_21") (pintype "input"))
    )
    (net (code "75") (name "Net-(M1A-~{ERR})") (class "Default")
      (node (ref "IC5") (pin "18") (pinfunction "18_18") (pintype "passive"))
      (node (ref "M1A") (pin "18") (pinfunction "~{ERR}_18") (pintype "output"))
    )
    (net (code "76") (name "Net-(M1A-~{HOME})") (class "Default")
      (node (ref "IC5") (pin "27") (pinfunction "27_27") (pintype "passive"))
      (node (ref "M1A") (pin "27") (pinfunction "~{HOME}_27") (pintype "output"))
    )
    (net (code "77") (name "Net-(M1A-~{RES})") (class "Default")
      (node (ref "IC5") (pin "16") (pinfunction "16_16") (pintype "passive"))
      (node (ref "M1A") (pin "16") (pinfunction "~{RES}_16") (pintype "input"))
    )
    (net (code "78") (name "Net-(M1A-~{SLP})") (class "Default")
      (node (ref "IC5") (pin "17") (pinfunction "17_17") (pintype "passive"))
      (node (ref "M1A") (pin "17") (pinfunction "~{SLP}_17") (pintype "input"))
    )
    (net (code "79") (name "Net-(M2-AOUT1)") (class "Default")
      (node (ref "M2") (pin "5") (pinfunction "AOUT1_5") (pintype "output"))
      (node (ref "MOTOR2") (pin "4") (pinfunction "4_4") (pintype "passive"))
      (node (ref "RA") (pin "5") (pinfunction "5_5") (pintype "passive"))
    )
    (net (code "80") (name "Net-(M2-AOUT2)") (class "Default")
      (node (ref "M2") (pin "7") (pinfunction "AOUT2_7") (pintype "output"))
      (node (ref "MOTOR2") (pin "3") (pinfunction "3_3") (pintype "passive"))
      (node (ref "RA") (pin "2") (pinfunction "2_2") (pintype "passive"))
    )
    (net (code "81") (name "Net-(M2-AVREF)") (class "Default")
      (node (ref "M2") (pin "12") (pinfunction "AVREF_12") (pintype "input"))
      (node (ref "M2") (pin "13") (pinfunction "BVREF_13") (pintype "input"))
      (node (ref "M2") (pin "15") (pinfunction "V3P3_15") (pintype "output"))
      (node (ref "M2") (pin "19") (pinfunction "DECAY_19") (pintype "input"))
    )
    (net (code "82") (name "Net-(M2-BOUT1)") (class "Default")
      (node (ref "M2") (pin "10") (pinfunction "BOUT1_10") (pintype "output"))
      (node (ref "MOTOR2") (pin "1") (pinfunction "1_1") (pintype "passive"))
      (node (ref "RA") (pin "3") (pinfunction "3_3") (pintype "passive"))
    )
    (net (code "83") (name "Net-(M2-BOUT2)") (class "Default")
      (node (ref "M2") (pin "8") (pinfunction "BOUT2_8") (pintype "output"))
      (node (ref "MOTOR2") (pin "2") (pinfunction "2_2") (pintype "passive"))
      (node (ref "RA") (pin "4") (pinfunction "4_4") (pintype "passive"))
    )
    (net (code "84") (name "Net-(M2-CP1)") (class "Default")
      (node (ref "C5") (pin "1") (pinfunction "1_1") (pintype "passive"))
      (node (ref "M2") (pin "1") (pinfunction "CP1_1") (pintype "passive"))
    )
    (net (code "85") (name "Net-(M2-CP2)") (class "Default")
      (node (ref "C5") (pin "2") (pinfunction "2_2") (pintype "passive"))
      (node (ref "M2") (pin "2") (pinfunction "CP2_2") (pintype "passive"))
    )
    (net (code "86") (name "Net-(M2-ISENA)") (class "Default")
      (node (ref "M2") (pin "6") (pinfunction "ISENA_6") (pintype "bidirectional"))
      (node (ref "R7") (pin "2") (pinfunction "2_2") (pintype "passive"))
      (node (ref "R8") (pin "2") (pinfunction "2_2") (pintype "passive"))
    )
    (net (code "87") (name "Net-(M2-ISENB)") (class "Default")
      (node (ref "M2") (pin "9") (pinfunction "ISENB_9") (pintype "bidirectional"))
      (node (ref "R10") (pin "2") (pinfunction "2_2") (pintype "passive"))
      (node (ref "R9") (pin "2") (pinfunction "2_2") (pintype "passive"))
    )
    (net (code "88") (name "Net-(M2A-AOUT1)") (class "Default")
      (node (ref "IC4") (pin "5") (pinfunction "5_5") (pintype "passive"))
      (node (ref "M2A") (pin "5") (pinfunction "AOUT1_5") (pintype "output"))
    )
    (net (code "89") (name "Net-(M2A-AOUT2)") (class "Default")
      (node (ref "IC4") (pin "7") (pinfunction "7_7") (pintype "passive"))
      (node (ref "M2A") (pin "7") (pinfunction "AOUT2_7") (pintype "output"))
    )
    (net (code "90") (name "Net-(M2A-AVREF)") (class "Default")
      (node (ref "IC4") (pin "12") (pinfunction "12_12") (pintype "passive"))
      (node (ref "M2A") (pin "12") (pinfunction "AVREF_12") (pintype "input"))
    )
    (net (code "91") (name "Net-(M2A-BOUT1)") (class "Default")
      (node (ref "IC4") (pin "10") (pinfunction "10_10") (pintype "passive"))
      (node (ref "M2A") (pin "10") (pinfunction "BOUT1_10") (pintype "output"))
    )
    (net (code "92") (name "Net-(M2A-BOUT2)") (class "Default")
      (node (ref "IC4") (pin "8") (pinfunction "8_8") (pintype "passive"))
      (node (ref "M2A") (pin "8") (pinfunction "BOUT2_8") (pintype "output"))
    )
    (net (code "93") (name "Net-(M2A-BVREF)") (class "Default")
      (node (ref "IC4") (pin "13") (pinfunction "13_13") (pintype "passive"))
      (node (ref "M2A") (pin "13") (pinfunction "BVREF_13") (pintype "input"))
    )
    (net (code "94") (name "Net-(M2A-CP1)") (class "Default")
      (node (ref "IC4") (pin "1") (pinfunction "1_1") (pintype "passive"))
      (node (ref "M2A") (pin "1") (pinfunction "CP1_1") (pintype "passive"))
    )
    (net (code "95") (name "Net-(M2A-CP2)") (class "Default")
      (node (ref "IC4") (pin "2") (pinfunction "2_2") (pintype "passive"))
      (node (ref "M2A") (pin "2") (pinfunction "CP2_2") (pintype "passive"))
    )
    (net (code "96") (name "Net-(M2A-DECAY)") (class "Default")
      (node (ref "IC4") (pin "19") (pinfunction "19_19") (pintype "passive"))
      (node (ref "M2A") (pin "19") (pinfunction "DECAY_19") (pintype "input"))
    )
    (net (code "97") (name "Net-(M2A-DIR)") (class "Default")
      (node (ref "IC4") (pin "20") (pinfunction "20_20") (pintype "passive"))
      (node (ref "M2A") (pin "20") (pinfunction "DIR_20") (pintype "input"))
    )
    (net (code "98") (name "Net-(M2A-GND2)") (class "Default")
      (node (ref "C2") (pin "2") (pinfunction "2_2") (pintype "passive"))
      (node (ref "C3") (pin "1") (pinfunction "1_1") (pintype "passive"))
      (node (ref "IC4") (pin "14") (pinfunction "14_14") (pintype "passive"))
      (node (ref "IC4") (pin "28") (pinfunction "28_28") (pintype "passive"))
      (node (ref "M2A") (pin "14") (pinfunction "GND1_14") (pintype "power_in"))
      (node (ref "M2A") (pin "28") (pinfunction "GND2_28") (pintype "power_in"))
      (node (ref "M2A") (pin "EXP") (pinfunction "GND1_EXP") (pintype "power_in"))
    )
    (net (code "99") (name "Net-(M2A-ISENA)") (class "Default")
      (node (ref "IC4") (pin "6") (pinfunction "6_6") (pintype "passive"))
      (node (ref "M2A") (pin "6") (pinfunction "ISENA_6") (pintype "bidirectional"))
    )
    (net (code "100") (name "Net-(M2A-ISENB)") (class "Default")
      (node (ref "IC4") (pin "9") (pinfunction "9_9") (pintype "passive"))
      (node (ref "M2A") (pin "9") (pinfunction "ISENB_9") (pintype "bidirectional"))
    )
    (net (code "101") (name "Net-(M2A-MODE0)") (class "Default")
      (node (ref "IC4") (pin "24") (pinfunction "24_24") (pintype "passive"))
      (node (ref "M2A") (pin "24") (pinfunction "MODE0_24") (pintype "input"))
    )
    (net (code "102") (name "Net-(M2A-MODE1)") (class "Default")
      (node (ref "IC4") (pin "25") (pinfunction "25_25") (pintype "passive"))
      (node (ref "M2A") (pin "25") (pinfunction "MODE1_25") (pintype "input"))
    )
    (net (code "103") (name "Net-(M2A-MODE2)") (class "Default")
      (node (ref "IC4") (pin "26") (pinfunction "26_26") (pintype "passive"))
      (node (ref "M2A") (pin "26") (pinfunction "MODE2_26") (pintype "input"))
    )
    (net (code "104") (name "Net-(M2A-STEP)") (class "Default")
      (node (ref "IC4") (pin "22") (pinfunction "22_22") (pintype "passive"))
      (node (ref "M2A") (pin "22") (pinfunction "STEP_22") (pintype "input"))
    )
    (net (code "105") (name "Net-(M2A-V3P3)") (class "Default")
      (node (ref "C2") (pin "1") (pinfunction "1_1") (pintype "passive"))
      (node (ref "IC4") (pin "15") (pinfunction "15_15") (pintype "passive"))
      (node (ref "M2A") (pin "15") (pinfunction "V3P3_15") (pintype "output"))
    )
    (net (code "106") (name "Net-(M2A-VCP)") (class "Default")
      (node (ref "C3") (pin "2") (pinfunction "2_2") (pintype "passive"))
      (node (ref "IC4") (pin "3") (pinfunction "3_3") (pintype "passive"))
      (node (ref "M2A") (pin "3") (pinfunction "VCP_3") (pintype "output"))
    )
    (net (code "107") (name "Net-(M2A-VMA)") (class "Default")
      (node (ref "IC4") (pin "4") (pinfunction "4_4") (pintype "passive"))
      (node (ref "M2A") (pin "4") (pinfunction "VMA_4") (pintype "power_in"))
    )
    (net (code "108") (name "Net-(M2A-VMB)") (class "Default")
      (node (ref "IC4") (pin "11") (pinfunction "11_11") (pintype "passive"))
      (node (ref "M2A") (pin "11") (pinfunction "VMB_11") (pintype "power_in"))
    )
    (net (code "109") (name "Net-(M2A-~{EN})") (class "Default")
      (node (ref "IC4") (pin "21") (pinfunction "21_21") (pintype "passive"))
      (node (ref "M2A") (pin "21") (pinfunction "~{EN}_21") (pintype "input"))
    )
    (net (code "110") (name "Net-(M2A-~{ERR})") (class "Default")
      (node (ref "IC4") (pin "18") (pinfunction "18_18") (pintype "passive"))
      (node (ref "M2A") (pin "18") (pinfunction "~{ERR}_18") (pintype "output"))
    )
    (net (code "111") (name "Net-(M2A-~{HOME})") (class "Default")
      (node (ref "IC4") (pin "27") (pinfunction "27_27") (pintype "passive"))
      (node (ref "M2A") (pin "27") (pinfunction "~{HOME}_27") (pintype "output"))
    )
    (net (code "112") (name "Net-(M2A-~{RES})") (class "Default")
      (node (ref "IC4") (pin "16") (pinfunction "16_16") (pintype "passive"))
      (node (ref "M2A") (pin "16") (pinfunction "~{RES}_16") (pintype "input"))
    )
    (net (code "113") (name "Net-(M2A-~{SLP})") (class "Default")
      (node (ref "IC4") (pin "17") (pinfunction "17_17") (pintype "passive"))
      (node (ref "M2A") (pin "17") (pinfunction "~{SLP}_17") (pintype "input"))
    )
    (net (code "114") (name "Net-(PWR-PadA)") (class "Default")
      (node (ref "PWR") (pin "A") (pinfunction "A_A") (pintype "passive"))
      (node (ref "R14") (pin "2") (pinfunction "2_2") (pintype "passive"))
    )
    (net (code "115") (name "Net-(R13-Pad2)") (class "Default")
      (node (ref "R13") (pin "2") (pinfunction "2_2") (pintype "passive"))
      (node (ref "STATUS") (pin "A") (pinfunction "A_A") (pintype "passive"))
    )
    (net (code "116") (name "Net-(R19-Pad1)") (class "Default")
      (node (ref "R19") (pin "1") (pinfunction "1_1") (pintype "passive"))
      (node (ref "USB") (pin "A") (pinfunction "A_A") (pintype "passive"))
    )
    (net (code "117") (name "V+") (class "Default")
      (node (ref "C10") (pin "1") (pinfunction "1_1") (pintype "passive"))
      (node (ref "C4") (pin "+") (pinfunction "+_+") (pintype "passive"))
      (node (ref "C8") (pin "+") (pinfunction "+_+") (pintype "passive"))
      (node (ref "D1") (pin "C") (pinfunction "C_C") (pintype "passive"))
      (node (ref "IC3") (pin "3") (pinfunction "IN_3") (pintype "input"))
      (node (ref "M1") (pin "11") (pinfunction "VMB_11") (pintype "power_in"))
      (node (ref "M1") (pin "4") (pinfunction "VMA_4") (pintype "power_in"))
      (node (ref "M2") (pin "11") (pinfunction "VMB_11") (pintype "power_in"))
      (node (ref "M2") (pin "4") (pinfunction "VMA_4") (pintype "power_in"))
    )
    (net (code "118") (name "unconnected-(DEC-Pad1)") (class "Default")
      (node (ref "DEC") (pin "1") (pinfunction "1_1") (pintype "passive"))
    )
    (net (code "119") (name "unconnected-(DEC-Pad6)") (class "Default")
      (node (ref "DEC") (pin "6") (pinfunction "6_6") (pintype "passive"))
    )
    (net (code "120") (name "unconnected-(IC1-PA4{slash}AD4{slash}PCINT4-Pad35)") (class "Default")
      (node (ref "IC1") (pin "35") (pinfunction "PA4/AD4/PCINT4_35") (pintype "bidirectional"))
    )
    (net (code "121") (name "unconnected-(IC1-PA5{slash}AD5{slash}PCINT5-Pad34)") (class "Default")
      (node (ref "IC1") (pin "34") (pinfunction "PA5/AD5/PCINT5_34") (pintype "bidirectional"))
    )
    (net (code "122") (name "unconnected-(IC1-PA6{slash}AD6{slash}PCINT6-Pad33)") (class "Default")
      (node (ref "IC1") (pin "33") (pinfunction "PA6/AD6/PCINT6_33") (pintype "bidirectional"))
    )
    (net (code "123") (name "unconnected-(IC1-PA7{slash}AD7{slash}PCINT7-Pad32)") (class "Default")
      (node (ref "IC1") (pin "32") (pinfunction "PA7/AD7/PCINT7_32") (pintype "bidirectional"))
    )
    (net (code "124") (name "unconnected-(IC1-PB1{slash}T1{slash}OC2-Pad2)") (class "Default")
      (node (ref "IC1") (pin "2") (pinfunction "PB1/T1/OC2_2") (pintype "bidirectional"))
    )
    (net (code "125") (name "unconnected-(IC1-PB4{slash}OC3B{slash}~{SS}-Pad5)") (class "Default")
      (node (ref "IC1") (pin "5") (pinfunction "PB4/OC3B/~{SS}_5") (pintype "bidirectional"))
    )
    (net (code "126") (name "unconnected-(IC1-PC0{slash}A8{slash}PCINT8-Pad21)") (class "Default")
      (node (ref "IC1") (pin "21") (pinfunction "PC0/A8/PCINT8_21") (pintype "bidirectional"))
    )
    (net (code "127") (name "unconnected-(IC1-PC1{slash}A9{slash}PCINT9-Pad22)") (class "Default")
      (node (ref "IC1") (pin "22") (pinfunction "PC1/A9/PCINT9_22") (pintype "bidirectional"))
    )
    (net (code "128") (name "unconnected-(IC1-PC2{slash}A10{slash}PCINT10-Pad23)") (class "Default")
      (node (ref "IC1") (pin "23") (pinfunction "PC2/A10/PCINT10_23") (pintype "bidirectional"))
    )
    (net (code "129") (name "unconnected-(IC1-PC3{slash}A11{slash}PCINT11-Pad24)") (class "Default")
      (node (ref "IC1") (pin "24") (pinfunction "PC3/A11/PCINT11_24") (pintype "bidirectional"))
    )
    (net (code "130") (name "unconnected-(IC1-PC4{slash}A12{slash}TCK{slash}PCINT12-Pad25)") (class "Default")
      (node (ref "IC1") (pin "25") (pinfunction "PC4/A12/TCK/PCINT12_25") (pintype "bidirectional"))
    )
    (net (code "131") (name "unconnected-(IC1-PC5{slash}A13{slash}TMS{slash}PCINT13-Pad26)") (class "Default")
      (node (ref "IC1") (pin "26") (pinfunction "PC5/A13/TMS/PCINT13_26") (pintype "bidirectional"))
    )
    (net (code "132") (name "unconnected-(IC1-PC6{slash}A14{slash}TDO{slash}PCINT14-Pad27)") (class "Default")
      (node (ref "IC1") (pin "27") (pinfunction "PC6/A14/TDO/PCINT14_27") (pintype "bidirectional"))
    )
    (net (code "133") (name "unconnected-(IC1-PC7{slash}A15{slash}TDI{slash}PCINT15-Pad28)") (class "Default")
      (node (ref "IC1") (pin "28") (pinfunction "PC7/A15/TDI/PCINT15_28") (pintype "bidirectional"))
    )
    (net (code "134") (name "unconnected-(IC1-PE0{slash}ICP1{slash}INT2-Pad31)") (class "Default")
      (node (ref "IC1") (pin "31") (pinfunction "PE0/ICP1/INT2_31") (pintype "bidirectional"))
    )
    (net (code "135") (name "unconnected-(IC1-PE1{slash}ALE-Pad30)") (class "Default")
      (node (ref "IC1") (pin "30") (pinfunction "PE1/ALE_30") (pintype "bidirectional"))
    )
    (net (code "136") (name "unconnected-(IC2-RB4{slash}AN10{slash}SDI{slash}SDA-Pad13)") (class "Default")
      (node (ref "IC2") (pin "13") (pinfunction "RB4/AN10/SDI/SDA_13") (pintype "bidirectional"))
    )
    (net (code "137") (name "unconnected-(IC2-RB6{slash}SCK{slash}SCL-Pad11)") (class "Default")
      (node (ref "IC2") (pin "11") (pinfunction "RB6/SCK/SCL_11") (pintype "bidirectional"))
    )
    (net (code "138") (name "unconnected-(IC2-RC1{slash}AN5{slash}C12IN1-{slash}INT1{slash}VREF--Pad15)") (class "Default")
      (node (ref "IC2") (pin "15") (pinfunction "RC1/AN5/C12IN1-/INT1/VREF-_15") (pintype "bidirectional"))
    )
    (net (code "139") (name "unconnected-(IC2-RC2{slash}AN6{slash}P1D{slash}C12IN2-{slash}CVREF{slash}INT2-Pad14)") (class "Default")
      (node (ref "IC2") (pin "14") (pinfunction "RC2/AN6/P1D/C12IN2-/CVREF/INT2_14") (pintype "bidirectional"))
    )
    (net (code "140") (name "unconnected-(IC2-RC3{slash}AN7{slash}P1C{slash}C12IN3-{slash}PGM-Pad7)") (class "Default")
      (node (ref "IC2") (pin "7") (pinfunction "RC3/AN7/P1C/C12IN3-/PGM_7") (pintype "bidirectional"))
    )
    (net (code "141") (name "unconnected-(IC2-RC4{slash}P1B{slash}C12OUT{slash}SRQ-Pad6)") (class "Default")
      (node (ref "IC2") (pin "6") (pinfunction "RC4/P1B/C12OUT/SRQ_6") (pintype "bidirectional"))
    )
    (net (code "142") (name "unconnected-(IC2-RC5{slash}CCP1{slash}P1A{slash}T0CKI-Pad5)") (class "Default")
      (node (ref "IC2") (pin "5") (pinfunction "RC5/CCP1/P1A/T0CKI_5") (pintype "bidirectional"))
    )
    (net (code "143") (name "unconnected-(IC2-RC6{slash}AN8{slash}~{SS{slash}T13CKI{slash}T1OSCI}-Pad8)") (class "Default")
      (node (ref "IC2") (pin "8") (pinfunction "RC6/AN8/~{SS/T13CKI/T1OSCI}_8") (pintype "bidirectional"))
    )
    (net (code "144") (name "unconnected-(IC4-Pad23)") (class "Default")
      (node (ref "IC4") (pin "23") (pinfunction "23_23") (pintype "passive"))
    )
    (net (code "145") (name "unconnected-(IC5-Pad23)") (class "Default")
      (node (ref "IC5") (pin "23") (pinfunction "23_23") (pintype "passive"))
    )
    (net (code "146") (name "unconnected-(M1-N{slash}C-Pad23)") (class "Default")
      (node (ref "M1") (pin "23") (pinfunction "N/C_23") (pintype "no_connect"))
    )
    (net (code "147") (name "unconnected-(M1-VCP-Pad3)") (class "Default")
      (node (ref "M1") (pin "3") (pinfunction "VCP_3") (pintype "output"))
    )
    (net (code "148") (name "unconnected-(M1A-N{slash}C-Pad23)") (class "Default")
      (node (ref "M1A") (pin "23") (pinfunction "N/C_23") (pintype "no_connect"))
    )
    (net (code "149") (name "unconnected-(M2-N{slash}C-Pad23)") (class "Default")
      (node (ref "M2") (pin "23") (pinfunction "N/C_23") (pintype "no_connect"))
    )
    (net (code "150") (name "unconnected-(M2-VCP-Pad3)") (class "Default")
      (node (ref "M2") (pin "3") (pinfunction "VCP_3") (pintype "output"))
    )
    (net (code "151") (name "unconnected-(M2A-N{slash}C-Pad23)") (class "Default")
      (node (ref "M2A") (pin "23") (pinfunction "N/C_23") (pintype "no_connect"))
    )
    (net (code "152") (name "unconnected-(RA-Pad1)") (class "Default")
      (node (ref "RA") (pin "1") (pinfunction "1_1") (pintype "passive"))
    )
    (net (code "153") (name "unconnected-(RA-Pad6)") (class "Default")
      (node (ref "RA") (pin "6") (pinfunction "6_6") (pintype "passive"))
    )
    (net (code "154") (name "unconnected-(USB->-PadID)") (class "Default")
      (node (ref "USB->") (pin "ID") (pinfunction "ID_ID") (pintype "bidirectional"))
    )
  )
)
